# espduino-12-panel.net
KiCad netlist of a schematic drawn in EAGLE
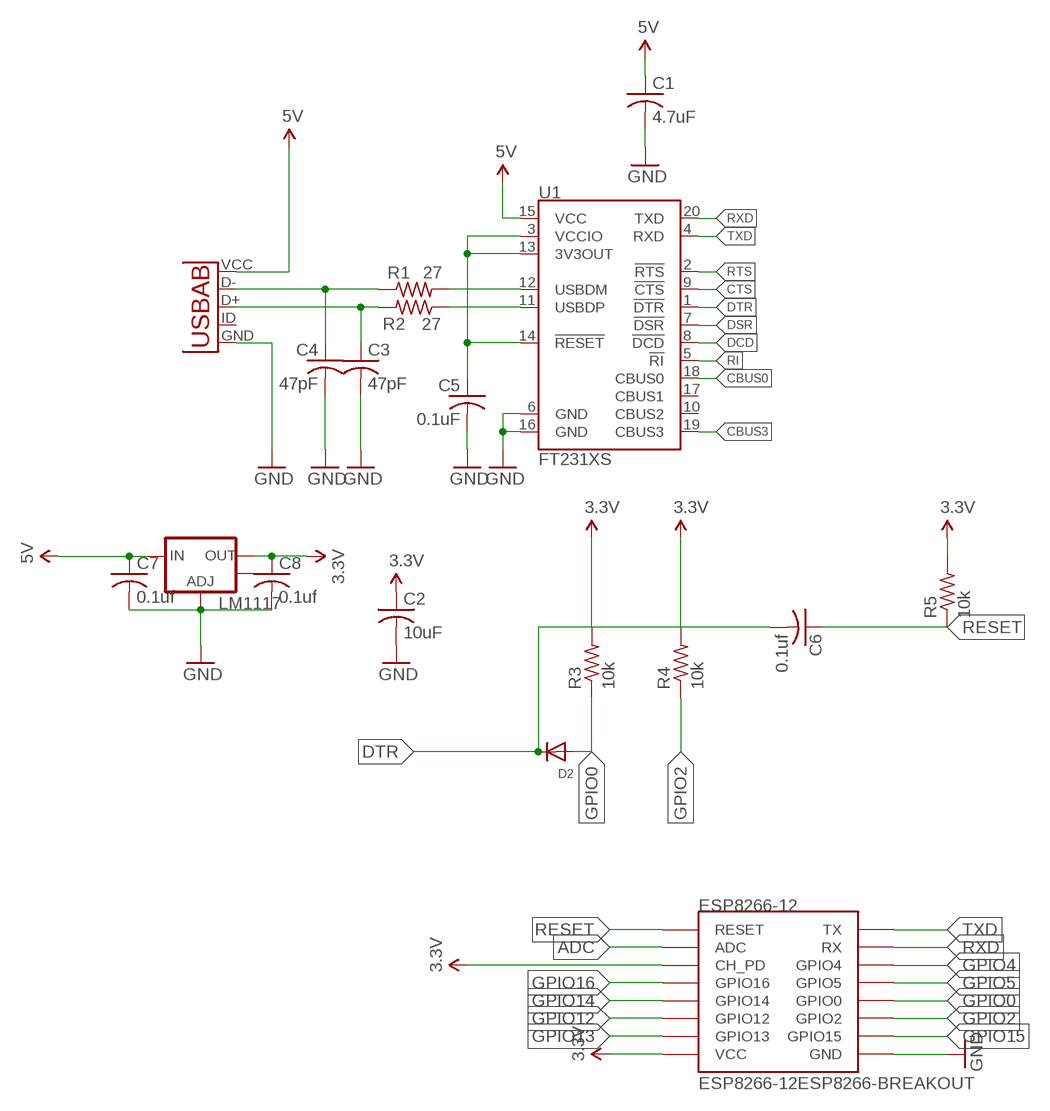
[diagram p0: schematic, sheet 1]

(export (version "E")
  (design (tool "Eeschema 10.0.6"))
  (components
    (comp (ref "C1")
      (value "4.7uF")
      (footprint "eagle-import:C0603")
      (libsource (lib "eagle-import") (part "C-USC0603"))
    )
    (comp (ref "C2")
      (value "10uF")
      (footprint "eagle-import:C0603")
      (libsource (lib "eagle-import") (part "C-USC0603"))
    )
    (comp (ref "C3")
      (value "47pF")
      (footprint "eagle-import:C0603")
      (libsource (lib "eagle-import") (part "C-USC0603"))
    )
    (comp (ref "C4")
      (value "47pF")
      (footprint "eagle-import:C0603")
      (libsource (lib "eagle-import") (part "C-USC0603"))
    )
    (comp (ref "C5")
      (value "0.1uF")
      (footprint "eagle-import:C0603")
      (libsource (lib "eagle-import") (part "C-USC0603"))
    )
    (comp (ref "C6")
      (value "0.1uf")
      (footprint "eagle-import:C0603")
      (libsource (lib "eagle-import") (part "C-USC0603"))
    )
    (comp (ref "C7")
      (value "0.1uf")
      (footprint "eagle-import:C0603")
      (libsource (lib "eagle-import") (part "C-USC0603"))
    )
    (comp (ref "C8")
      (value "0.1uf")
      (footprint "eagle-import:C0603")
      (libsource (lib "eagle-import") (part "C-USC0603"))
    )
    (comp (ref "D2")
      (value "DIODESOT23_REFLOW")
      (footprint "eagle-import:SOT23-R")
      (libsource (lib "eagle-import") (part "DIODESOT23_REFLOW"))
    )
    (comp (ref "ESP8266-12")
      (value "ESP8266-12ESP8266-BREAKOUT")
      (footprint "eagle-import:ESP8266-12-EXT-HEADERS")
      (libsource (lib "eagle-import") (part "ESP8266-12ESP8266-BREAKOUT"))
    )
    (comp (ref "LM1117")
      (value "V_REG_LM1117SOT223")
      (footprint "eagle-import:SOT223")
      (libsource (lib "eagle-import") (part "V_REG_LM1117SOT223"))
    )
    (comp (ref "R1")
      (value "27")
      (footprint "eagle-import:R0603")
      (libsource (lib "eagle-import") (part "R-US_R0603"))
    )
    (comp (ref "R2")
      (value "27")
      (footprint "eagle-import:R0603")
      (libsource (lib "eagle-import") (part "R-US_R0603"))
    )
    (comp (ref "R3")
      (value "10k")
      (footprint "eagle-import:R0603")
      (libsource (lib "eagle-import") (part "R-US_R0603"))
    )
    (comp (ref "R4")
      (value "10k")
      (footprint "eagle-import:R0603")
      (libsource (lib "eagle-import") (part "R-US_R0603"))
    )
    (comp (ref "R5")
      (value "10k")
      (footprint "eagle-import:R0603")
      (libsource (lib "eagle-import") (part "R-US_R0603"))
    )
    (comp (ref "U1")
      (value "FT231XS")
      (footprint "eagle-import:SSOP20_L")
      (libsource (lib "eagle-import") (part "FT231XS"))
    )
    (comp (ref "U2")
      (value "USB-AB")
      (footprint "eagle-import:MICRO-USB-A01SB141B1")
      (libsource (lib "eagle-import") (part "USB-AB"))
    )
  )
  (nets
    (net (code "1") (name "3.3V") (class "Default")
      (node (ref "C2") (pin "1") (pinfunction "1_1") (pintype "passive"))
      (node (ref "C8") (pin "1") (pinfunction "1_1") (pintype "passive"))
      (node (ref "ESP8266-12") (pin "CH_PD") (pinfunction "CH_PD_CH_PD") (pintype "bidirectional"))
      (node (ref "ESP8266-12") (pin "VCC") (pinfunction "VCC_VCC") (pintype "bidirectional"))
      (node (ref "ESP8266-12") (pin "VCC_P") (pinfunction "VCC_VCC_P") (pintype "bidirectional"))
      (node (ref "LM1117") (pin "2") (pinfunction "OUT_2") (pintype "output"))
      (node (ref "R3") (pin "2") (pinfunction "2_2") (pintype "passive"))
      (node (ref "R4") (pin "2") (pinfunction "2_2") (pintype "passive"))
      (node (ref "R5") (pin "2") (pinfunction "2_2") (pintype "passive"))
    )
    (net (code "2") (name "5V") (class "Default")
      (node (ref "C1") (pin "1") (pinfunction "1_1") (pintype "passive"))
      (node (ref "C7") (pin "1") (pinfunction "1_1") (pintype "passive"))
      (node (ref "LM1117") (pin "3") (pinfunction "IN_3") (pintype "input"))
      (node (ref "U1") (pin "15") (pinfunction "VCC_15") (pintype "bidirectional"))
      (node (ref "U2") (pin "VCC") (pinfunction "VBUS_VCC") (pintype "bidirectional"))
    )
    (net (code "3") (name "ADC") (class "Default")
      (node (ref "ESP8266-12") (pin "ADC") (pinfunction "ADC_ADC") (pintype "bidirectional"))
      (node (ref "ESP8266-12") (pin "ADC_P") (pinfunction "ADC_ADC_P") (pintype "bidirectional"))
    )
    (net (code "4") (name "CBUS0") (class "Default")
      (node (ref "U1") (pin "18") (pinfunction "CBUS0_18") (pintype "bidirectional"))
    )
    (net (code "5") (name "CBUS3") (class "Default")
      (node (ref "U1") (pin "19") (pinfunction "CBUS3_19") (pintype "bidirectional"))
    )
    (net (code "6") (name "CTS") (class "Default")
      (node (ref "U1") (pin "9") (pinfunction "~{CTS}_9") (pintype "bidirectional"))
    )
    (net (code "7") (name "DCD") (class "Default")
      (node (ref "U1") (pin "8") (pinfunction "~{DCD}_8") (pintype "bidirectional"))
    )
    (net (code "8") (name "DSR") (class "Default")
      (node (ref "U1") (pin "7") (pinfunction "~{DSR}_7") (pintype "bidirectional"))
    )
    (net (code "9") (name "DTR") (class "Default")
      (node (ref "C6") (pin "2") (pinfunction "2_2") (pintype "passive"))
      (node (ref "D2") (pin "3") (pinfunction "C_3") (pintype "passive"))
      (node (ref "U1") (pin "1") (pinfunction "~{DTR}_1") (pintype "bidirectional"))
    )
    (net (code "10") (name "GND") (class "Default")
      (node (ref "C1") (pin "2") (pinfunction "2_2") (pintype "passive"))
      (node (ref "C2") (pin "2") (pinfunction "2_2") (pintype "passive"))
      (node (ref "C3") (pin "2") (pinfunction "2_2") (pintype "passive"))
      (node (ref "C4") (pin "2") (pinfunction "2_2") (pintype "passive"))
      (node (ref "C5") (pin "2") (pinfunction "2_2") (pintype "passive"))
      (node (ref "C7") (pin "2") (pinfunction "2_2") (pintype "passive"))
      (node (ref "C8") (pin "2") (pinfunction "2_2") (pintype "passive"))
      (node (ref "ESP8266-12") (pin "GND") (pinfunction "GND_GND") (pintype "bidirectional"))
      (node (ref "ESP8266-12") (pin "GND_P") (pinfunction "GND_GND_P") (pintype "bidirectional"))
      (node (ref "LM1117") (pin "1") (pinfunction "ADJ_1") (pintype "input"))
      (node (ref "U1") (pin "16") (pinfunction "GND_16") (pintype "bidirectional"))
      (node (ref "U1") (pin "6") (pinfunction "GND_6") (pintype "bidirectional"))
      (node (ref "U2") (pin "GND") (pinfunction "GND_GND") (pintype "bidirectional"))
    )
    (net (code "11") (name "GPIO0") (class "Default")
      (node (ref "D2") (pin "1") (pinfunction "A_1") (pintype "passive"))
      (node (ref "ESP8266-12") (pin "GPIO0") (pinfunction "GPIO0_GPIO0") (pintype "bidirectional"))
      (node (ref "ESP8266-12") (pin "GPIO0_P") (pinfunction "GPIO0_GPIO0_P") (pintype "bidirectional"))
      (node (ref "R3") (pin "1") (pinfunction "1_1") (pintype "passive"))
    )
    (net (code "12") (name "GPIO2") (class "Default")
      (node (ref "ESP8266-12") (pin "GPIO2") (pinfunction "GPIO2_GPIO2") (pintype "bidirectional"))
      (node (ref "ESP8266-12") (pin "GPIO2_P") (pinfunction "GPIO2_GPIO2_P") (pintype "bidirectional"))
      (node (ref "R4") (pin "1") (pinfunction "1_1") (pintype "passive"))
    )
    (net (code "13") (name "GPIO4") (class "Default")
      (node (ref "ESP8266-12") (pin "GPIO4") (pinfunction "GPIO4_GPIO4") (pintype "bidirectional"))
      (node (ref "ESP8266-12") (pin "GPIO4_P") (pinfunction "GPIO4_GPIO4_P") (pintype "bidirectional"))
    )
    (net (code "14") (name "GPIO5") (class "Default")
      (node (ref "ESP8266-12") (pin "GPIO5") (pinfunction "GPIO5_GPIO5") (pintype "bidirectional"))
      (node (ref "ESP8266-12") (pin "GPIO5_P") (pinfunction "GPIO5_GPIO5_P") (pintype "bidirectional"))
    )
    (net (code "15") (name "GPIO12") (class "Default")
      (node (ref "ESP8266-12") (pin "GPIO12") (pinfunction "GPIO12_GPIO12") (pintype "bidirectional"))
      (node (ref "ESP8266-12") (pin "GPIO12_P") (pinfunction "GPIO12_GPIO12_P") (pintype "bidirectional"))
    )
    (net (code "16") (name "GPIO13") (class "Default")
      (node (ref "ESP8266-12") (pin "GPIO13") (pinfunction "GPIO13_GPIO13") (pintype "bidirectional"))
      (node (ref "ESP8266-12") (pin "GPIO13_P") (pinfunction "GPIO13_GPIO13_P") (pintype "bidirectional"))
    )
    (net (code "17") (name "GPIO14") (class "Default")
      (node (ref "ESP8266-12") (pin "GPIO14") (pinfunction "GPIO14_GPIO14") (pintype "bidirectional"))
      (node (ref "ESP8266-12") (pin "GPIO14_P") (pinfunction "GPIO14_GPIO14_P") (pintype "bidirectional"))
    )
    (net (code "18") (name "GPIO15") (class "Default")
      (node (ref "ESP8266-12") (pin "GPIO15") (pinfunction "GPIO15_GPIO15") (pintype "bidirectional"))
      (node (ref "ESP8266-12") (pin "GPIO15_P") (pinfunction "GPIO15_GPIO15_P") (pintype "bidirectional"))
    )
    (net (code "19") (name "GPIO16") (class "Default")
      (node (ref "ESP8266-12") (pin "GPIO16") (pinfunction "GPIO16_GPIO16") (pintype "bidirectional"))
      (node (ref "ESP8266-12") (pin "GPIO_16_P") (pinfunction "GPIO16_GPIO_16_P") (pintype "bidirectional"))
    )
    (net (code "20") (name "Net-(C3-Pad1)") (class "Default")
      (node (ref "C3") (pin "1") (pinfunction "1_1") (pintype "passive"))
      (node (ref "R2") (pin "2") (pinfunction "2_2") (pintype "passive"))
      (node (ref "U2") (pin "D+") (pinfunction "D+_D+") (pintype "bidirectional"))
    )
    (net (code "21") (name "Net-(C4-Pad1)") (class "Default")
      (node (ref "C4") (pin "1") (pinfunction "1_1") (pintype "passive"))
      (node (ref "R1") (pin "1") (pinfunction "1_1") (pintype "passive"))
      (node (ref "U2") (pin "D-") (pinfunction "D-_D-") (pintype "bidirectional"))
    )
    (net (code "22") (name "Net-(U1-3V3OUT)") (class "Default")
      (node (ref "C5") (pin "1") (pinfunction "1_1") (pintype "passive"))
      (node (ref "U1") (pin "13") (pinfunction "3V3OUT_13") (pintype "bidirectional"))
      (node (ref "U1") (pin "14") (pinfunction "~{RESET}_14") (pintype "bidirectional"))
      (node (ref "U1") (pin "3") (pinfunction "VCCIO_3") (pintype "bidirectional"))
    )
    (net (code "23") (name "Net-(U1-USBDM)") (class "Default")
      (node (ref "R1") (pin "2") (pinfunction "2_2") (pintype "passive"))
      (node (ref "U1") (pin "12") (pinfunction "USBDM_12") (pintype "bidirectional"))
    )
    (net (code "24") (name "Net-(U1-USBDP)") (class "Default")
      (node (ref "R2") (pin "1") (pinfunction "1_1") (pintype "passive"))
      (node (ref "U1") (pin "11") (pinfunction "USBDP_11") (pintype "bidirectional"))
    )
    (net (code "25") (name "RESET") (class "Default")
      (node (ref "C6") (pin "1") (pinfunction "1_1") (pintype "passive"))
      (node (ref "ESP8266-12") (pin "RESET") (pinfunction "RESET_RESET") (pintype "bidirectional"))
      (node (ref "R5") (pin "1") (pinfunction "1_1") (pintype "passive"))
    )
    (net (code "26") (name "RI") (class "Default")
      (node (ref "U1") (pin "5") (pinfunction "~{RI}_5") (pintype "bidirectional"))
    )
    (net (code "27") (name "RTS") (class "Default")
      (node (ref "U1") (pin "2") (pinfunction "~{RTS}_2") (pintype "bidirectional"))
    )
    (net (code "28") (name "RXD") (class "Default")
      (node (ref "ESP8266-12") (pin "RX") (pinfunction "RX_RX") (pintype "bidirectional"))
      (node (ref "U1") (pin "20") (pinfunction "TXD_20") (pintype "bidirectional"))
    )
    (net (code "29") (name "TXD") (class "Default")
      (node (ref "ESP8266-12") (pin "TX") (pinfunction "TX_TX") (pintype "bidirectional"))
      (node (ref "U1") (pin "4") (pinfunction "RXD_4") (pintype "bidirectional"))
    )
    (net (code "30") (name "unconnected-(LM1117-OUT-Pad4)") (class "Default")
      (node (ref "LM1117") (pin "4") (pinfunction "OUT_4") (pintype "output"))
    )
    (net (code "31") (name "unconnected-(U1-CBUS1-Pad17)") (class "Default")
      (node (ref "U1") (pin "17") (pinfunction "CBUS1_17") (pintype "bidirectional"))
    )
    (net (code "32") (name "unconnected-(U1-CBUS2-Pad10)") (class "Default")
      (node (ref "U1") (pin "10") (pinfunction "CBUS2_10") (pintype "bidirectional"))
    )
    (net (code "33") (name "unconnected-(U2-USBID-PadID)") (class "Default")
      (node (ref "U2") (pin "ID") (pinfunction "USBID_ID") (pintype "bidirectional"))
    )
  )
)
